# driver.net
KiCad netlist of a schematic drawn in EAGLE
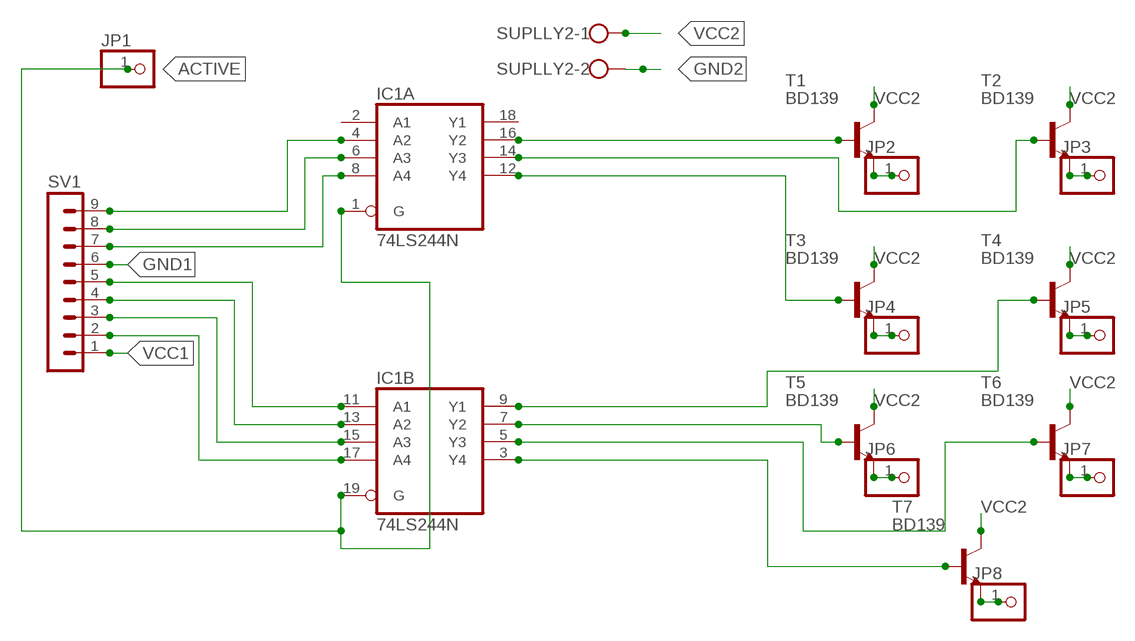
[diagram p0: schematic, sheet 1]

(export (version "E")
  (design (tool "Eeschema 10.0.6"))
  (components
    (comp (ref "IC1")
      (value "74LS244N")
      (footprint "eagle-import:DIL20")
      (libsource (lib "eagle-import") (part "74244NLS"))
    )
    (comp (ref "JP1")
      (value "PINHD-1X1")
      (footprint "eagle-import:1X01")
      (libsource (lib "eagle-import") (part "PINHD-1X1"))
    )
    (comp (ref "JP2")
      (value "PINHD-1X1")
      (footprint "eagle-import:1X01")
      (libsource (lib "eagle-import") (part "PINHD-1X1"))
    )
    (comp (ref "JP3")
      (value "PINHD-1X1")
      (footprint "eagle-import:1X01")
      (libsource (lib "eagle-import") (part "PINHD-1X1"))
    )
    (comp (ref "JP4")
      (value "PINHD-1X1")
      (footprint "eagle-import:1X01")
      (libsource (lib "eagle-import") (part "PINHD-1X1"))
    )
    (comp (ref "JP5")
      (value "PINHD-1X1")
      (footprint "eagle-import:1X01")
      (libsource (lib "eagle-import") (part "PINHD-1X1"))
    )
    (comp (ref "JP6")
      (value "PINHD-1X1")
      (footprint "eagle-import:1X01")
      (libsource (lib "eagle-import") (part "PINHD-1X1"))
    )
    (comp (ref "JP7")
      (value "PINHD-1X1")
      (footprint "eagle-import:1X01")
      (libsource (lib "eagle-import") (part "PINHD-1X1"))
    )
    (comp (ref "JP8")
      (value "PINHD-1X1")
      (footprint "eagle-import:1X01")
      (libsource (lib "eagle-import") (part "PINHD-1X1"))
    )
    (comp (ref "SUPLLY2")
      (value "W237-102")
      (footprint "eagle-import:W237-102")
      (fields (field (name "MPN") "237-102"))
      (libsource (lib "eagle-import") (part "W237-102"))
    )
    (comp (ref "SV1")
      (value "MA09-1")
      (footprint "eagle-import:MA09-1")
      (libsource (lib "eagle-import") (part "MA09-1"))
    )
    (comp (ref "T1")
      (value "BD139")
      (footprint "eagle-import:TO126")
      (libsource (lib "eagle-import") (part "BD139"))
    )
    (comp (ref "T2")
      (value "BD139")
      (footprint "eagle-import:TO126")
      (libsource (lib "eagle-import") (part "BD139"))
    )
    (comp (ref "T3")
      (value "BD139")
      (footprint "eagle-import:TO126")
      (libsource (lib "eagle-import") (part "BD139"))
    )
    (comp (ref "T4")
      (value "BD139")
      (footprint "eagle-import:TO126")
      (libsource (lib "eagle-import") (part "BD139"))
    )
    (comp (ref "T5")
      (value "BD139")
      (footprint "eagle-import:TO126")
      (libsource (lib "eagle-import") (part "BD139"))
    )
    (comp (ref "T6")
      (value "BD139")
      (footprint "eagle-import:TO126")
      (libsource (lib "eagle-import") (part "BD139"))
    )
    (comp (ref "T7")
      (value "BD139")
      (footprint "eagle-import:TO126")
      (libsource (lib "eagle-import") (part "BD139"))
    )
  )
  (nets
    (net (code "1") (name "ACTIVE") (class "Default")
      (node (ref "IC1") (pin "1") (pinfunction "G_1") (pintype "input"))
      (node (ref "IC1") (pin "19") (pinfunction "G_19") (pintype "input"))
      (node (ref "JP1") (pin "1") (pinfunction "1_1") (pintype "passive"))
    )
    (net (code "2") (name "GND1") (class "Default")
      (node (ref "SV1") (pin "6") (pinfunction "6_6") (pintype "passive"))
    )
    (net (code "3") (name "GND2") (class "Default")
      (node (ref "SUPLLY2") (pin "2") (pinfunction "KL_2") (pintype "passive"))
    )
    (net (code "4") (name "Net-(IC1A-A2)") (class "Default")
      (node (ref "IC1") (pin "4") (pinfunction "A2_4") (pintype "input"))
      (node (ref "SV1") (pin "9") (pinfunction "9_9") (pintype "passive"))
    )
    (net (code "5") (name "Net-(IC1A-A3)") (class "Default")
      (node (ref "IC1") (pin "6") (pinfunction "A3_6") (pintype "input"))
      (node (ref "SV1") (pin "8") (pinfunction "8_8") (pintype "passive"))
    )
    (net (code "6") (name "Net-(IC1A-A4)") (class "Default")
      (node (ref "IC1") (pin "8") (pinfunction "A4_8") (pintype "input"))
      (node (ref "SV1") (pin "7") (pinfunction "7_7") (pintype "passive"))
    )
    (net (code "7") (name "Net-(IC1A-Y2)") (class "Default")
      (node (ref "IC1") (pin "16") (pinfunction "Y2_16") (pintype "tri_state"))
      (node (ref "T1") (pin "3") (pinfunction "B_3") (pintype "passive"))
    )
    (net (code "8") (name "Net-(IC1A-Y3)") (class "Default")
      (node (ref "IC1") (pin "14") (pinfunction "Y3_14") (pintype "tri_state"))
      (node (ref "T2") (pin "3") (pinfunction "B_3") (pintype "passive"))
    )
    (net (code "9") (name "Net-(IC1A-Y4)") (class "Default")
      (node (ref "IC1") (pin "12") (pinfunction "Y4_12") (pintype "tri_state"))
      (node (ref "T3") (pin "3") (pinfunction "B_3") (pintype "passive"))
    )
    (net (code "10") (name "Net-(IC1B-A1)") (class "Default")
      (node (ref "IC1") (pin "11") (pinfunction "A1_11") (pintype "input"))
      (node (ref "SV1") (pin "5") (pinfunction "5_5") (pintype "passive"))
    )
    (net (code "11") (name "Net-(IC1B-A2)") (class "Default")
      (node (ref "IC1") (pin "13") (pinfunction "A2_13") (pintype "input"))
      (node (ref "SV1") (pin "4") (pinfunction "4_4") (pintype "passive"))
    )
    (net (code "12") (name "Net-(IC1B-A3)") (class "Default")
      (node (ref "IC1") (pin "15") (pinfunction "A3_15") (pintype "input"))
      (node (ref "SV1") (pin "3") (pinfunction "3_3") (pintype "passive"))
    )
    (net (code "13") (name "Net-(IC1B-A4)") (class "Default")
      (node (ref "IC1") (pin "17") (pinfunction "A4_17") (pintype "input"))
      (node (ref "SV1") (pin "2") (pinfunction "2_2") (pintype "passive"))
    )
    (net (code "14") (name "Net-(IC1B-Y1)") (class "Default")
      (node (ref "IC1") (pin "9") (pinfunction "Y1_9") (pintype "tri_state"))
      (node (ref "T4") (pin "3") (pinfunction "B_3") (pintype "passive"))
    )
    (net (code "15") (name "Net-(IC1B-Y2)") (class "Default")
      (node (ref "IC1") (pin "7") (pinfunction "Y2_7") (pintype "tri_state"))
      (node (ref "T5") (pin "3") (pinfunction "B_3") (pintype "passive"))
    )
    (net (code "16") (name "Net-(IC1B-Y3)") (class "Default")
      (node (ref "IC1") (pin "5") (pinfunction "Y3_5") (pintype "tri_state"))
      (node (ref "T6") (pin "3") (pinfunction "B_3") (pintype "passive"))
    )
    (net (code "17") (name "Net-(IC1B-Y4)") (class "Default")
      (node (ref "IC1") (pin "3") (pinfunction "Y4_3") (pintype "tri_state"))
      (node (ref "T7") (pin "3") (pinfunction "B_3") (pintype "passive"))
    )
    (net (code "18") (name "Net-(T1-E)") (class "Default")
      (node (ref "JP2") (pin "1") (pinfunction "1_1") (pintype "passive"))
      (node (ref "T1") (pin "1") (pinfunction "E_1") (pintype "passive"))
    )
    (net (code "19") (name "Net-(T2-E)") (class "Default")
      (node (ref "JP3") (pin "1") (pinfunction "1_1") (pintype "passive"))
      (node (ref "T2") (pin "1") (pinfunction "E_1") (pintype "passive"))
    )
    (net (code "20") (name "Net-(T3-E)") (class "Default")
      (node (ref "JP4") (pin "1") (pinfunction "1_1") (pintype "passive"))
      (node (ref "T3") (pin "1") (pinfunction "E_1") (pintype "passive"))
    )
    (net (code "21") (name "Net-(T4-E)") (class "Default")
      (node (ref "JP5") (pin "1") (pinfunction "1_1") (pintype "passive"))
      (node (ref "T4") (pin "1") (pinfunction "E_1") (pintype "passive"))
    )
    (net (code "22") (name "Net-(T5-E)") (class "Default")
      (node (ref "JP6") (pin "1") (pinfunction "1_1") (pintype "passive"))
      (node (ref "T5") (pin "1") (pinfunction "E_1") (pintype "passive"))
    )
    (net (code "23") (name "Net-(T6-E)") (class "Default")
      (node (ref "JP7") (pin "1") (pinfunction "1_1") (pintype "passive"))
      (node (ref "T6") (pin "1") (pinfunction "E_1") (pintype "passive"))
    )
    (net (code "24") (name "Net-(T7-E)") (class "Default")
      (node (ref "JP8") (pin "1") (pinfunction "1_1") (pintype "passive"))
      (node (ref "T7") (pin "1") (pinfunction "E_1") (pintype "passive"))
    )
    (net (code "25") (name "VCC1") (class "Default")
      (node (ref "SV1") (pin "1") (pinfunction "1_1") (pintype "passive"))
    )
    (net (code "26") (name "VCC2") (class "Default")
      (node (ref "SUPLLY2") (pin "1") (pinfunction "KL_1") (pintype "passive"))
      (node (ref "T1") (pin "2") (pinfunction "C_2") (pintype "passive"))
      (node (ref "T2") (pin "2") (pinfunction "C_2") (pintype "passive"))
      (node (ref "T3") (pin "2") (pinfunction "C_2") (pintype "passive"))
      (node (ref "T4") (pin "2") (pinfunction "C_2") (pintype "passive"))
      (node (ref "T5") (pin "2") (pinfunction "C_2") (pintype "passive"))
      (node (ref "T6") (pin "2") (pinfunction "C_2") (pintype "passive"))
      (node (ref "T7") (pin "2") (pinfunction "C_2") (pintype "passive"))
    )
    (net (code "27") (name "unconnected-(IC1A-A1-Pad2)") (class "Default")
      (node (ref "IC1") (pin "2") (pinfunction "A1_2") (pintype "input"))
    )
    (net (code "28") (name "unconnected-(IC1A-Y1-Pad18)") (class "Default")
      (node (ref "IC1") (pin "18") (pinfunction "Y1_18") (pintype "tri_state"))
    )
  )
)
